# mcp3426_sample.net
KiCad netlist of a schematic drawn in EAGLE
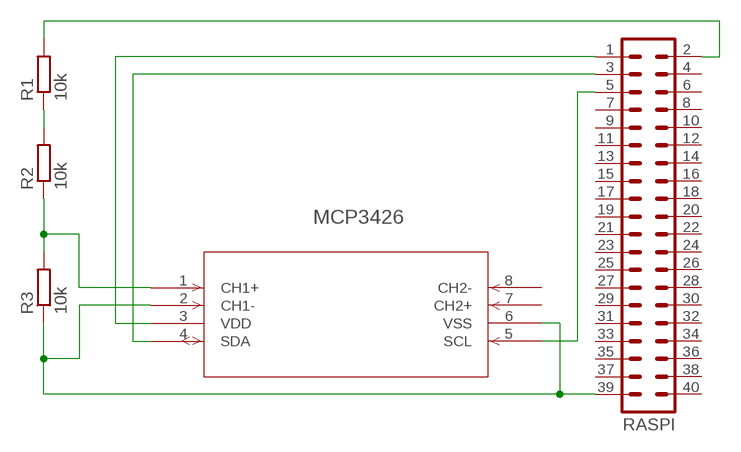
[diagram p0: schematic, sheet 1]

(export (version "E")
  (design (tool "Eeschema 10.0.6"))
  (components
    (comp (ref "MCP3426")
      (value "MCP3422-XXXX_MS")
      (footprint "eagle-import:MSOP8_MC")
      (libsource (lib "eagle-import") (part "MCP3422-XXXX_MS"))
    )
    (comp (ref "R1")
      (value "10k")
      (footprint "eagle-import:0207_10")
      (libsource (lib "eagle-import") (part "R-EU_0207/10"))
    )
    (comp (ref "R2")
      (value "10k")
      (footprint "eagle-import:0207_10")
      (libsource (lib "eagle-import") (part "R-EU_0207/10"))
    )
    (comp (ref "R3")
      (value "10k")
      (footprint "eagle-import:0207_10")
      (libsource (lib "eagle-import") (part "R-EU_0207/10"))
    )
    (comp (ref "RASPI")
      (value "ML40")
      (footprint "eagle-import:ML40")
      (libsource (lib "eagle-import") (part "ML40"))
    )
  )
  (nets
    (net (code "1") (name "Net-(MCP3426-CH1+)") (class "Default")
      (node (ref "MCP3426") (pin "1") (pinfunction "CH1+_1") (pintype "input"))
      (node (ref "R2") (pin "1") (pinfunction "1_1") (pintype "passive"))
      (node (ref "R3") (pin "2") (pinfunction "2_2") (pintype "passive"))
    )
    (net (code "2") (name "Net-(MCP3426-CH1-)") (class "Default")
      (node (ref "MCP3426") (pin "2") (pinfunction "CH1-_2") (pintype "input"))
      (node (ref "MCP3426") (pin "6") (pinfunction "VSS_6") (pintype "power_in"))
      (node (ref "R3") (pin "1") (pinfunction "1_1") (pintype "passive"))
      (node (ref "RASPI") (pin "39") (pinfunction "39_39") (pintype "passive"))
    )
    (net (code "3") (name "Net-(MCP3426-SCL)") (class "Default")
      (node (ref "MCP3426") (pin "5") (pinfunction "SCL_5") (pintype "input"))
      (node (ref "RASPI") (pin "5") (pinfunction "5_5") (pintype "passive"))
    )
    (net (code "4") (name "Net-(MCP3426-SDA)") (class "Default")
      (node (ref "MCP3426") (pin "4") (pinfunction "SDA_4") (pintype "bidirectional"))
      (node (ref "RASPI") (pin "3") (pinfunction "3_3") (pintype "passive"))
    )
    (net (code "5") (name "Net-(MCP3426-VDD)") (class "Default")
      (node (ref "MCP3426") (pin "3") (pinfunction "VDD_3") (pintype "power_in"))
      (node (ref "RASPI") (pin "1") (pinfunction "1_1") (pintype "passive"))
    )
    (net (code "6") (name "Net-(R1-Pad1)") (class "Default")
      (node (ref "R1") (pin "1") (pinfunction "1_1") (pintype "passive"))
      (node (ref "R2") (pin "2") (pinfunction "2_2") (pintype "passive"))
    )
    (net (code "7") (name "Net-(R1-Pad2)") (class "Default")
      (node (ref "R1") (pin "2") (pinfunction "2_2") (pintype "passive"))
      (node (ref "RASPI") (pin "2") (pinfunction "2_2") (pintype "passive"))
    )
    (net (code "8") (name "unconnected-(MCP3426-CH2+-Pad7)") (class "Default")
      (node (ref "MCP3426") (pin "7") (pinfunction "CH2+_7") (pintype "input"))
    )
    (net (code "9") (name "unconnected-(MCP3426-CH2--Pad8)") (class "Default")
      (node (ref "MCP3426") (pin "8") (pinfunction "CH2-_8") (pintype "input"))
    )
    (net (code "10") (name "unconnected-(RASPI-Pad4)") (class "Default")
      (node (ref "RASPI") (pin "4") (pinfunction "4_4") (pintype "passive"))
    )
    (net (code "11") (name "unconnected-(RASPI-Pad6)") (class "Default")
      (node (ref "RASPI") (pin "6") (pinfunction "6_6") (pintype "passive"))
    )
    (net (code "12") (name "unconnected-(RASPI-Pad7)") (class "Default")
      (node (ref "RASPI") (pin "7") (pinfunction "7_7") (pintype "passive"))
    )
    (net (code "13") (name "unconnected-(RASPI-Pad8)") (class "Default")
      (node (ref "RASPI") (pin "8") (pinfunction "8_8") (pintype "passive"))
    )
    (net (code "14") (name "unconnected-(RASPI-Pad9)") (class "Default")
      (node (ref "RASPI") (pin "9") (pinfunction "9_9") (pintype "passive"))
    )
    (net (code "15") (name "unconnected-(RASPI-Pad10)") (class "Default")
      (node (ref "RASPI") (pin "10") (pinfunction "10_10") (pintype "passive"))
    )
    (net (code "16") (name "unconnected-(RASPI-Pad11)") (class "Default")
      (node (ref "RASPI") (pin "11") (pinfunction "11_11") (pintype "passive"))
    )
    (net (code "17") (name "unconnected-(RASPI-Pad12)") (class "Default")
      (node (ref "RASPI") (pin "12") (pinfunction "12_12") (pintype "passive"))
    )
    (net (code "18") (name "unconnected-(RASPI-Pad13)") (class "Default")
      (node (ref "RASPI") (pin "13") (pinfunction "13_13") (pintype "passive"))
    )
    (net (code "19") (name "unconnected-(RASPI-Pad14)") (class "Default")
      (node (ref "RASPI") (pin "14") (pinfunction "14_14") (pintype "passive"))
    )
    (net (code "20") (name "unconnected-(RASPI-Pad15)") (class "Default")
      (node (ref "RASPI") (pin "15") (pinfunction "15_15") (pintype "passive"))
    )
    (net (code "21") (name "unconnected-(RASPI-Pad16)") (class "Default")
      (node (ref "RASPI") (pin "16") (pinfunction "16_16") (pintype "passive"))
    )
    (net (code "22") (name "unconnected-(RASPI-Pad17)") (class "Default")
      (node (ref "RASPI") (pin "17") (pinfunction "17_17") (pintype "passive"))
    )
    (net (code "23") (name "unconnected-(RASPI-Pad18)") (class "Default")
      (node (ref "RASPI") (pin "18") (pinfunction "18_18") (pintype "passive"))
    )
    (net (code "24") (name "unconnected-(RASPI-Pad19)") (class "Default")
      (node (ref "RASPI") (pin "19") (pinfunction "19_19") (pintype "passive"))
    )
    (net (code "25") (name "unconnected-(RASPI-Pad20)") (class "Default")
      (node (ref "RASPI") (pin "20") (pinfunction "20_20") (pintype "passive"))
    )
    (net (code "26") (name "unconnected-(RASPI-Pad21)") (class "Default")
      (node (ref "RASPI") (pin "21") (pinfunction "21_21") (pintype "passive"))
    )
    (net (code "27") (name "unconnected-(RASPI-Pad22)") (class "Default")
      (node (ref "RASPI") (pin "22") (pinfunction "22_22") (pintype "passive"))
    )
    (net (code "28") (name "unconnected-(RASPI-Pad23)") (class "Default")
      (node (ref "RASPI") (pin "23") (pinfunction "23_23") (pintype "passive"))
    )
    (net (code "29") (name "unconnected-(RASPI-Pad24)") (class "Default")
      (node (ref "RASPI") (pin "24") (pinfunction "24_24") (pintype "passive"))
    )
    (net (code "30") (name "unconnected-(RASPI-Pad25)") (class "Default")
      (node (ref "RASPI") (pin "25") (pinfunction "25_25") (pintype "passive"))
    )
    (net (code "31") (name "unconnected-(RASPI-Pad26)") (class "Default")
      (node (ref "RASPI") (pin "26") (pinfunction "26_26") (pintype "passive"))
    )
    (net (code "32") (name "unconnected-(RASPI-Pad27)") (class "Default")
      (node (ref "RASPI") (pin "27") (pinfunction "27_27") (pintype "passive"))
    )
    (net (code "33") (name "unconnected-(RASPI-Pad28)") (class "Default")
      (node (ref "RASPI") (pin "28") (pinfunction "28_28") (pintype "passive"))
    )
    (net (code "34") (name "unconnected-(RASPI-Pad29)") (class "Default")
      (node (ref "RASPI") (pin "29") (pinfunction "29_29") (pintype "passive"))
    )
    (net (code "35") (name "unconnected-(RASPI-Pad30)") (class "Default")
      (node (ref "RASPI") (pin "30") (pinfunction "30_30") (pintype "passive"))
    )
    (net (code "36") (name "unconnected-(RASPI-Pad31)") (class "Default")
      (node (ref "RASPI") (pin "31") (pinfunction "31_31") (pintype "passive"))
    )
    (net (code "37") (name "unconnected-(RASPI-Pad32)") (class "Default")
      (node (ref "RASPI") (pin "32") (pinfunction "32_32") (pintype "passive"))
    )
    (net (code "38") (name "unconnected-(RASPI-Pad33)") (class "Default")
      (node (ref "RASPI") (pin "33") (pinfunction "33_33") (pintype "passive"))
    )
    (net (code "39") (name "unconnected-(RASPI-Pad34)") (class "Default")
      (node (ref "RASPI") (pin "34") (pinfunction "34_34") (pintype "passive"))
    )
    (net (code "40") (name "unconnected-(RASPI-Pad35)") (class "Default")
      (node (ref "RASPI") (pin "35") (pinfunction "35_35") (pintype "passive"))
    )
    (net (code "41") (name "unconnected-(RASPI-Pad36)") (class "Default")
      (node (ref "RASPI") (pin "36") (pinfunction "36_36") (pintype "passive"))
    )
    (net (code "42") (name "unconnected-(RASPI-Pad37)") (class "Default")
      (node (ref "RASPI") (pin "37") (pinfunction "37_37") (pintype "passive"))
    )
    (net (code "43") (name "unconnected-(RASPI-Pad38)") (class "Default")
      (node (ref "RASPI") (pin "38") (pinfunction "38_38") (pintype "passive"))
    )
    (net (code "44") (name "unconnected-(RASPI-Pad40)") (class "Default")
      (node (ref "RASPI") (pin "40") (pinfunction "40_40") (pintype "passive"))
    )
  )
)
